# PoE.net
KiCad netlist of a schematic drawn in Altium Designer
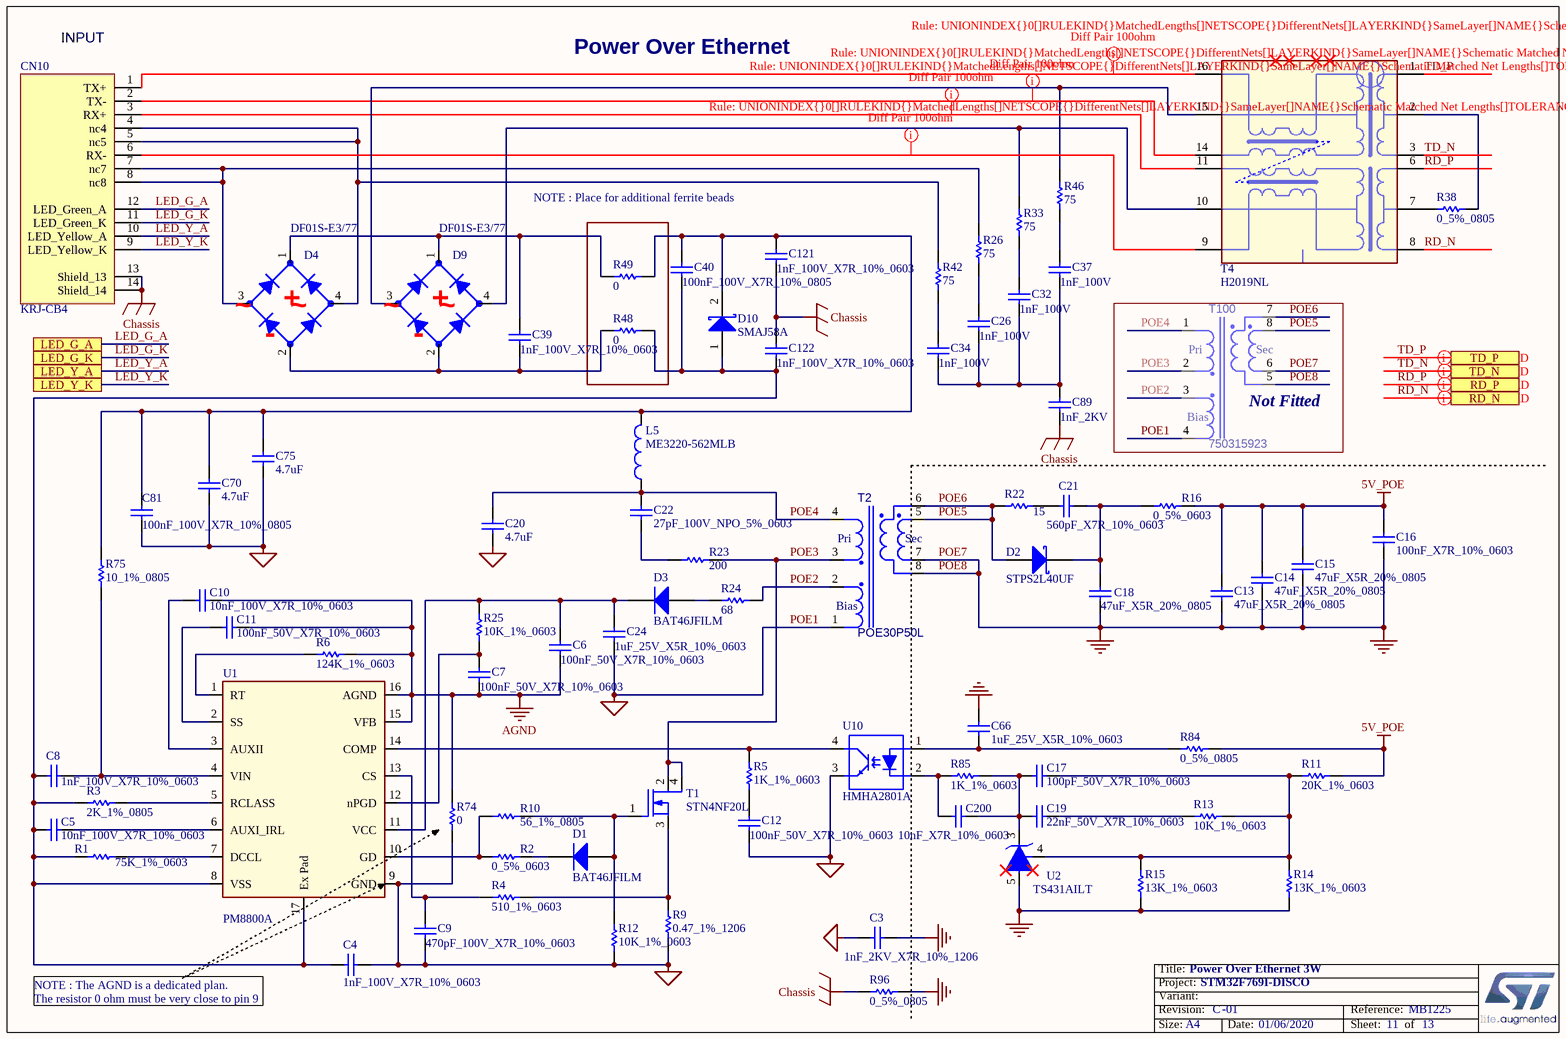
[diagram p0: PoE.SchDoc]

(export (version "E")
  (design (tool "Eeschema 10.0.6"))
  (components
    (comp (ref "C3")
      (value "1nF_2KV_X7R_10%_1206")
      (footprint "1206C")
      (description "Capacitor,1nF,2KV,X7R,10%,1206,YAGEO")
      (libsource (lib "MCD_TOOLS_CAPACITOR") (part "Cap_1nF_2KV_X7R_10%_1206"))
    )
    (comp (ref "C4")
      (value "1nF_100V_X7R_10%_0603")
      (footprint "0603C")
      (description "Capacitor,1nF,100V,X7R,10%,0603,YAGEO")
      (libsource (lib "MCD_TOOLS_CAPACITOR") (part "Cap_1nF_100V_X7R_10%_0603"))
    )
    (comp (ref "C5")
      (value "10nF_100V_X7R_10%_0603")
      (footprint "0603C")
      (description "Capacitor,10nF,100V,X7R,10%,0603,YAGEO")
      (libsource (lib "MCD_TOOLS_CAPACITOR") (part "Cap_10nF_100V_X7R_10%_0603"))
    )
    (comp (ref "C6")
      (value "100nF_50V_X7R_10%_0603")
      (footprint "0603C")
      (description "Capacitor,100nF,50V,X7R,10%,0603,YAGEO")
      (libsource (lib "MCD_TOOLS_CAPACITOR") (part "Cap_100nF_50V_X7R_10%_0603"))
    )
    (comp (ref "C7")
      (value "100nF_50V_X7R_10%_0603")
      (footprint "0603C")
      (description "Capacitor,100nF,50V,X7R,10%,0603,YAGEO")
      (libsource (lib "MCD_TOOLS_CAPACITOR") (part "Cap_100nF_50V_X7R_10%_0603"))
    )
    (comp (ref "C8")
      (value "1nF_100V_X7R_10%_0603")
      (footprint "0603C")
      (description "Capacitor,1nF,100V,X7R,10%,0603,YAGEO")
      (libsource (lib "MCD_TOOLS_CAPACITOR") (part "Cap_1nF_100V_X7R_10%_0603"))
    )
    (comp (ref "C9")
      (value "470pF_100V_X7R_10%_0603")
      (footprint "0603C")
      (description "Capacitor,470pF,100V,X7R,10%,0603,AVX")
      (libsource (lib "MCD_TOOLS_CAPACITOR") (part "Cap_470pF_100V_X7R_10%_0603"))
    )
    (comp (ref "C10")
      (value "10nF_100V_X7R_10%_0603")
      (footprint "0603C")
      (description "Capacitor,10nF,100V,X7R,10%,0603,YAGEO")
      (libsource (lib "MCD_TOOLS_CAPACITOR") (part "Cap_10nF_100V_X7R_10%_0603"))
    )
    (comp (ref "C11")
      (value "100nF_50V_X7R_10%_0603")
      (footprint "0603C")
      (description "Capacitor,100nF,50V,X7R,10%,0603,YAGEO")
      (libsource (lib "MCD_TOOLS_CAPACITOR") (part "Cap_100nF_50V_X7R_10%_0603"))
    )
    (comp (ref "C12")
      (value "100nF_50V_X7R_10%_0603")
      (footprint "0603C")
      (description "Capacitor,100nF,50V,X7R,10%,0603,YAGEO")
      (libsource (lib "MCD_TOOLS_CAPACITOR") (part "Cap_100nF_50V_X7R_10%_0603"))
    )
    (comp (ref "C13")
      (value "47uF_X5R_20%_0805")
      (footprint "0805C")
      (description "Capacitor,47uF,10V,X5R,20%,0805,MURATA")
      (libsource (lib "MCD_TOOLS_CAPACITOR") (part "Cap_47uF_X5R_20%_0805"))
    )
    (comp (ref "C14")
      (value "47uF_X5R_20%_0805")
      (footprint "0805C")
      (description "Capacitor,47uF,10V,X5R,20%,0805,MURATA")
      (libsource (lib "MCD_TOOLS_CAPACITOR") (part "Cap_47uF_X5R_20%_0805"))
    )
    (comp (ref "C15")
      (value "47uF_X5R_20%_0805")
      (footprint "0805C")
      (description "Capacitor,47uF,10V,X5R,20%,0805,MURATA")
      (libsource (lib "MCD_TOOLS_CAPACITOR") (part "Cap_47uF_X5R_20%_0805"))
    )
    (comp (ref "C16")
      (value "100nF_X7R_10%_0603")
      (footprint "0603C")
      (description "Capacitor,100nF,16V,X7R,10%,0603,YAGEO")
      (libsource (lib "MCD_TOOLS_CAPACITOR") (part "Cap_100nF_X7R_10%_0603"))
    )
    (comp (ref "C17")
      (value "100pF_50V_X7R_10%_0603")
      (footprint "0603C")
      (description "Capacitor,100pF,50V,X7R,10%,0603,AVX")
      (libsource (lib "MCD_TOOLS_CAPACITOR") (part "Cap_100pF_50V_X7R_10%_0603"))
    )
    (comp (ref "C18")
      (value "47uF_X5R_20%_0805")
      (footprint "0805C")
      (description "Capacitor,47uF,10V,X5R,20%,0805,MURATA")
      (libsource (lib "MCD_TOOLS_CAPACITOR") (part "Cap_47uF_X5R_20%_0805"))
    )
    (comp (ref "C19")
      (value "22nF_50V_X7R_10%_0603")
      (footprint "0603C")
      (description "Capacitor,22nF,50V,X7R,10%,0603,YAGEO")
      (libsource (lib "MCD_TOOLS_CAPACITOR") (part "Cap_22nF_50V_X7R_10%_0603"))
    )
    (comp (ref "C20")
      (value "4.7uF")
      (footprint "C1210_H2P5")
      (description "Capacitor, MLCC, 4.7uF, 100V, X7S, +/-10%, 1210 , T=2.5mm")
      (fields (field (name "INTERNAL_PART_NUMBER") "MCD-02212") (field (name "MANUFACTURER") "TDK"))
      (libsource (lib "MCD_PARTS_database") (part "Capacitor"))
    )
    (comp (ref "C21")
      (value "560pF_X7R_10%_0603")
      (footprint "0603C")
      (description "Capacitor,560pF,16V,X7R,10%,0603,AVX")
      (libsource (lib "MCD_TOOLS_CAPACITOR") (part "Cap_560pF_X7R_10%_0603"))
    )
    (comp (ref "C22")
      (value "27pF_100V_NPO_5%_0603")
      (footprint "0603C")
      (description "Capacitor,27pF,100V,NPO,5%,0603,YAGEO")
      (libsource (lib "MCD_TOOLS_CAPACITOR") (part "Cap_27pF_100V_NPO_5%_0603"))
    )
    (comp (ref "C24")
      (value "1uF_25V_X5R_10%_0603")
      (footprint "0603C")
      (description "Capacitor,1uF,25V,X5R,10%,0603,YAGEO")
      (libsource (lib "MCD_TOOLS_CAPACITOR") (part "Cap_1uF_25V_X5R_10%_0603"))
    )
    (comp (ref "C26")
      (value "1nF_100V")
      (footprint "0603C")
      (description "Capacitor,1nF,100V,X7R,10%,0603,YAGEO")
      (libsource (lib "MCD_TOOLS_CAPACITOR") (part "Cap_1nF_100V_X7R_10%_0603"))
    )
    (comp (ref "C32")
      (value "1nF_100V")
      (footprint "0603C")
      (description "Capacitor,1nF,100V,X7R,10%,0603,YAGEO")
      (libsource (lib "MCD_TOOLS_CAPACITOR") (part "Cap_1nF_100V_X7R_10%_0603"))
    )
    (comp (ref "C34")
      (value "1nF_100V")
      (footprint "0603C")
      (description "Capacitor,1nF,100V,X7R,10%,0603,YAGEO")
      (libsource (lib "MCD_TOOLS_CAPACITOR") (part "Cap_1nF_100V_X7R_10%_0603"))
    )
    (comp (ref "C37")
      (value "1nF_100V")
      (footprint "0603C")
      (description "Capacitor,1nF,100V,X7R,10%,0603,YAGEO")
      (libsource (lib "MCD_TOOLS_CAPACITOR") (part "Cap_1nF_100V_X7R_10%_0603"))
    )
    (comp (ref "C39")
      (value "1nF_100V_X7R_10%_0603")
      (footprint "0603C")
      (description "Capacitor,1nF,100V,X7R,10%,0603,YAGEO")
      (libsource (lib "MCD_TOOLS_CAPACITOR") (part "Cap_1nF_100V_X7R_10%_0603"))
    )
    (comp (ref "C40")
      (value "100nF_100V_X7R_10%_0805")
      (footprint "0805C")
      (description "Capacitor,100nF,100V,X7R,10%,0805,TDK")
      (libsource (lib "MCD_TOOLS_CAPACITOR") (part "Cap_100nF_100V_X7R_10%_0805"))
    )
    (comp (ref "C66")
      (value "1uF_25V_X5R_10%_0603")
      (footprint "0603C")
      (description "Capacitor,1uF,25V,X5R,10%,0603,YAGEO")
      (libsource (lib "MCD_TOOLS_CAPACITOR") (part "Cap_1uF_25V_X5R_10%_0603"))
    )
    (comp (ref "C70")
      (value "4.7uF")
      (footprint "C1210_H2P5")
      (description "Capacitor, MLCC, 4.7uF, 100V, X7S, +/-10%, 1210 , T=2.5mm")
      (fields (field (name "INTERNAL_PART_NUMBER") "MCD-02212") (field (name "MANUFACTURER") "TDK"))
      (libsource (lib "MCD_PARTS_database") (part "Capacitor"))
    )
    (comp (ref "C75")
      (value "4.7uF")
      (footprint "C1210_H2P5")
      (description "Capacitor, MLCC, 4.7uF, 100V, X7S, +/-10%, 1210 , T=2.5mm")
      (fields (field (name "INTERNAL_PART_NUMBER") "MCD-02212") (field (name "MANUFACTURER") "TDK"))
      (libsource (lib "MCD_PARTS_database") (part "Capacitor"))
    )
    (comp (ref "C81")
      (value "100nF_100V_X7R_10%_0805")
      (footprint "0805C")
      (description "Capacitor,100nF,100V,X7R,10%,0805,TDK")
      (libsource (lib "MCD_TOOLS_CAPACITOR") (part "Cap_100nF_100V_X7R_10%_0805"))
    )
    (comp (ref "C89")
      (value "1nF_2KV")
      (footprint "1206C")
      (description "Capacitor,1nF,2KV,X7R,10%,1206,YAGEO")
      (libsource (lib "MCD_TOOLS_CAPACITOR") (part "Cap_1nF_2KV_X7R_10%_1206"))
    )
    (comp (ref "C121")
      (value "1nF_100V_X7R_10%_0603")
      (footprint "0603C")
      (description "Capacitor,1nF,100V,X7R,10%,0603,YAGEO")
      (libsource (lib "MCD_TOOLS_CAPACITOR") (part "Cap_1nF_100V_X7R_10%_0603"))
    )
    (comp (ref "C122")
      (value "1nF_100V_X7R_10%_0603")
      (footprint "0603C")
      (description "Capacitor,1nF,100V,X7R,10%,0603,YAGEO")
      (libsource (lib "MCD_TOOLS_CAPACITOR") (part "Cap_1nF_100V_X7R_10%_0603"))
    )
    (comp (ref "C200")
      (value "10nF_X7R_10%_0603")
      (footprint "0603C")
      (description "Capacitor,10nF,50V,X7R,10%,0603,YAGEO")
      (libsource (lib "MCD_TOOLS_CAPACITOR") (part "Cap_10nF_X7R_10%_0603"))
    )
    (comp (ref "CN10")
      (value "KRJ-CB4")
      (footprint "RJ45_LED_KRJ-CB4R2GYZNL_EM")
      (description "100 Base-TX (Fast Ethernet)  RJ45 single port (1x1) with LEDS Integrated Connector")
      (libsource (lib "MCD_TOOLS_CONNECTOR") (part "KRJ-CB4"))
    )
    (comp (ref "D1")
      (value "BAT46JFILM")
      (footprint "SOD-323")
      (description "Schottky Single diode(150mA, 100V)")
      (libsource (lib "MCD_TOOLS_MISCELLANEOUS") (part "BAT46JFILM"))
    )
    (comp (ref "D2")
      (value "STPS2L40UF")
      (footprint "SMB")
      (description "Low drop power Schottky rectifier(2A, 40V, 0.34V)")
      (libsource (lib "MCD_TOOLS_MISCELLANEOUS") (part "STPS2L40UF"))
    )
    (comp (ref "D3")
      (value "BAT46JFILM")
      (footprint "SOD-323")
      (description "Schottky Single diode(150mA, 100V)")
      (libsource (lib "MCD_TOOLS_MISCELLANEOUS") (part "BAT46JFILM"))
    )
    (comp (ref "D4")
      (value "DF01S-E3/77")
      (footprint "BRF_VISHAY_DFS_DF01S")
      (description "Surface Mount Bridge Rectifier 1A 100V")
      (fields (field (name "INTERNAL_PART_NUMBER") "MCD-02211") (field (name "MANUFACTURER") "VISHAY"))
      (libsource (lib "MCD_PARTS_database") (part "DF01S_SMD"))
    )
    (comp (ref "D9")
      (value "DF01S-E3/77")
      (footprint "BRF_VISHAY_DFS_DF01S")
      (description "Surface Mount Bridge Rectifier 1A 100V")
      (fields (field (name "INTERNAL_PART_NUMBER") "MCD-02211") (field (name "MANUFACTURER") "VISHAY"))
      (libsource (lib "MCD_PARTS_database") (part "DF01S_SMD"))
    )
    (comp (ref "D10")
      (value "SMAJ58A")
      (footprint "SMA")
      (description "Transil 400W, VRM=58V")
      (libsource (lib "MCD_TOOLS_MISCELLANEOUS") (part "SMAJ58A"))
    )
    (comp (ref "L5")
      (value "ME3220-562MLB")
      (footprint "LSM2_3R2X2R8_H2")
      (description "Power Inductor, 5.6uH, 0.2R, ME3220-562ML, CoilCraft")
      (libsource (lib "MCD_TOOLS_MISCELLANEOUS") (part "ME3220-562ML"))
    )
    (comp (ref "R1")
      (value "75K_1%_0603")
      (footprint "0603R")
      (description "Resistor,75K,0603,1%,YAGEO")
      (libsource (lib "MCD_TOOLS_RESISTOR") (part "Res_75K_1%_0603"))
    )
    (comp (ref "R2")
      (value "0_5%_0603")
      (footprint "0603R-GS")
      (description "Resistor,0,0603,5%,YAGEO")
      (libsource (lib "MCD_TOOLS_RESISTOR") (part "Res_0_5%_0603"))
    )
    (comp (ref "R3")
      (value "2K_1%_0805")
      (footprint "0805R")
      (description "Resistor,2K,0805,1%,YAGEO")
      (libsource (lib "MCD_TOOLS_RESISTOR") (part "Res_2K_1%_0805"))
    )
    (comp (ref "R4")
      (value "510_1%_0603")
      (footprint "0603R")
      (description "Resistor,510,0603,1%,YAGEO")
      (libsource (lib "MCD_TOOLS_RESISTOR") (part "Res_510_1%_0603"))
    )
    (comp (ref "R5")
      (value "1K_1%_0603")
      (footprint "0603R")
      (description "Resistor,1K,0603,1%,YAGEO")
      (libsource (lib "MCD_TOOLS_RESISTOR") (part "Res_1K_1%_0603"))
    )
    (comp (ref "R6")
      (value "124K_1%_0603")
      (footprint "0603R")
      (description "Resistor,124K,0603,1%,YAGEO")
      (libsource (lib "MCD_TOOLS_RESISTOR") (part "Res_124K_1%_0603"))
    )
    (comp (ref "R9")
      (value "0.47_1%_1206")
      (footprint "1206R")
      (description "Resistor,0.47,1206,1%,YAGEO")
      (libsource (lib "MCD_TOOLS_RESISTOR") (part "Res_0.47_1%_1206"))
    )
    (comp (ref "R10")
      (value "56_1%_0805")
      (footprint "0805R")
      (description "Resistor,56,0805,1%,YAGEO")
      (libsource (lib "MCD_TOOLS_RESISTOR") (part "Res_56_1%_0805"))
    )
    (comp (ref "R11")
      (value "20K_1%_0603")
      (footprint "0603R")
      (description "Resistor,20K,0603,1%,YAGEO")
      (libsource (lib "MCD_TOOLS_RESISTOR") (part "Res_20K_1%_0603"))
    )
    (comp (ref "R12")
      (value "10K_1%_0603")
      (footprint "0603R")
      (description "Resistor,10K,0603,1%,YAGEO")
      (libsource (lib "MCD_TOOLS_RESISTOR") (part "Res_10K_1%_0603"))
    )
    (comp (ref "R13")
      (value "10K_1%_0603")
      (footprint "0603R")
      (description "Resistor,10K,0603,1%,YAGEO")
      (libsource (lib "MCD_TOOLS_RESISTOR") (part "Res_10K_1%_0603"))
    )
    (comp (ref "R14")
      (value "13K_1%_0603")
      (footprint "0603R")
      (description "Resistor,13K,0603,1%,YAGEO")
      (libsource (lib "MCD_TOOLS_RESISTOR") (part "Res_13K_1%_0603"))
    )
    (comp (ref "R15")
      (value "13K_1%_0603")
      (footprint "0603R")
      (description "Resistor,13K,0603,1%,YAGEO")
      (libsource (lib "MCD_TOOLS_RESISTOR") (part "Res_13K_1%_0603"))
    )
    (comp (ref "R16")
      (value "0_5%_0603")
      (footprint "0603R-GS")
      (description "Resistor,0,0603,5%,YAGEO")
      (libsource (lib "MCD_TOOLS_RESISTOR") (part "Res_0_5%_0603"))
    )
    (comp (ref "R22")
      (value "15")
      (footprint "0805R")
      (description "Resistor,15,0805,1%,YAGEO")
      (libsource (lib "MCD_TOOLS_RESISTOR") (part "Res_15_1%_0805"))
    )
    (comp (ref "R23")
      (value "200")
      (footprint "1206R")
      (description "Resistor,200,1206,1%,Rohm")
      (libsource (lib "MCD_TOOLS_RESISTOR") (part "Res_200_1%_1206"))
    )
    (comp (ref "R24")
      (value "68")
      (footprint "0805R")
      (description "Resistor,68,0805,1%,YAGEO")
      (libsource (lib "MCD_TOOLS_RESISTOR") (part "Res_68_1%_0805"))
    )
    (comp (ref "R25")
      (value "10K_1%_0603")
      (footprint "0603R")
      (description "Resistor,10K,0603,1%,YAGEO")
      (libsource (lib "MCD_TOOLS_RESISTOR") (part "Res_10K_1%_0603"))
    )
    (comp (ref "R26")
      (value "75")
      (footprint "0805R")
      (description "Resistor,75,0805,1%,YAGEO")
      (libsource (lib "MCD_TOOLS_RESISTOR") (part "Res_75_1%_0805"))
    )
    (comp (ref "R33")
      (value "75")
      (footprint "0805R")
      (description "Resistor,75,0805,1%,YAGEO")
      (libsource (lib "MCD_TOOLS_RESISTOR") (part "Res_75_1%_0805"))
    )
    (comp (ref "R38")
      (value "0_5%_0805")
      (footprint "0805R")
      (description "Resistor,0,0805,5%,YAGEO")
      (libsource (lib "MCD_TOOLS_RESISTOR") (part "Res_0_5%_0805"))
    )
    (comp (ref "R42")
      (value "75")
      (footprint "0805R")
      (description "Resistor,75,0805,1%,YAGEO")
      (libsource (lib "MCD_TOOLS_RESISTOR") (part "Res_75_1%_0805"))
    )
    (comp (ref "R46")
      (value "75")
      (footprint "0805R")
      (description "Resistor,75,0805,1%,YAGEO")
      (libsource (lib "MCD_TOOLS_RESISTOR") (part "Res_75_1%_0805"))
    )
    (comp (ref "R48")
      (value "0")
      (footprint "0805R")
      (description "Resistor,0,0805,5%,YAGEO")
      (libsource (lib "MCD_TOOLS_RESISTOR") (part "Res_0_5%_0805"))
    )
    (comp (ref "R49")
      (value "0")
      (footprint "0805R")
      (description "Resistor,0,0805,5%,YAGEO")
      (libsource (lib "MCD_TOOLS_RESISTOR") (part "Res_0_5%_0805"))
    )
    (comp (ref "R74")
      (value "0")
      (footprint "0603R-GS")
      (description "Resistor,0,0603,5%,YAGEO")
      (libsource (lib "MCD_TOOLS_RESISTOR") (part "Res_0_5%_0603"))
    )
    (comp (ref "R75")
      (value "10_1%_0805")
      (footprint "0805R")
      (description "Resistor,10,0805,1%,Stackpole,1/4W")
      (libsource (lib "MCD_TOOLS_RESISTOR") (part "Res_10_1%_0805"))
    )
    (comp (ref "R84")
      (value "0_5%_0805")
      (footprint "0805R")
      (description "Resistor,0,0805,5%,YAGEO")
      (libsource (lib "MCD_TOOLS_RESISTOR") (part "Res_0_5%_0805"))
    )
    (comp (ref "R85")
      (value "1K_1%_0603")
      (footprint "0603R")
      (description "Resistor,1K,0603,1%,YAGEO")
      (libsource (lib "MCD_TOOLS_RESISTOR") (part "Res_1K_1%_0603"))
    )
    (comp (ref "R96")
      (value "0_5%_0805")
      (footprint "0805R")
      (description "Resistor,0,0805,5%,YAGEO")
      (libsource (lib "MCD_TOOLS_RESISTOR") (part "Res_0_5%_0805"))
    )
    (comp (ref "T1")
      (value "STN4NF20L")
      (footprint "SOT-223")
      (description "N-channel 200 V, 1.1ohm, 1 A, low gate charge STripFET II, Power MOSFET")
      (libsource (lib "MCD_TOOLS_MISCELLANEOUS") (part "STN4NF20L"))
    )
    (comp (ref "T2")
      (value "POE30P50L")
      (footprint "TF_10R9X13R2-12R2X14R4_CPT")
      (description "Flyback Transformers for 3 Watt, PoE applications, CoilCraft Cyntec")
      (fields (field (name "PROVIDED") "Sub Co"))
      (libsource (lib "MCD_TOOLS_MISCELLANEOUS") (part "POE30P_C"))
    )
    (comp (ref "T4")
      (value "H2019NL")
      (footprint "TF_16SM_12R7X9R65")
      (description "10/100BASE-TX VoIP Magnetics Modules, Data Transformer")
      (libsource (lib "MCD_TOOLS_MISCELLANEOUS") (part "H2019"))
    )
    (comp (ref "T100")
      (value "750315923")
      (footprint "TF_8SM_12R04X12R85")
      (description "Flyback Transformers for 3 Watt, PoE applications, Wurth")
      (fields (field (name "PROVIDED") "Sub Co"))
      (libsource (lib "MCD_TOOLS_MISCELLANEOUS") (part "POE30P_W"))
    )
    (comp (ref "U1")
      (value "PM8800A")
      (footprint "TSSOP16_0R65_5x6R4_TP")
      (fields (field (name "PROVIDED") "STM"))
      (libsource (lib "MCD_TOOLS_MISCELLANEOUS") (part "PM8800A"))
    )
    (comp (ref "U2")
      (value "TS431AILT")
      (footprint "SOT23-5")
      (description "Low voltage adjustable shunt reference")
      (libsource (lib "MCD_TOOLS_MISCELLANEOUS") (part "TS431AILT"))
    )
    (comp (ref "U10")
      (value "HMHA2801A")
      (footprint "PC_4SM_1R27_2R5X6R8")
      (description "OPTOISOLATOR 3.7KV TRANSISTOR 4SMD")
      (libsource (lib "mb1225") (part "HMHA2801A"))
    )
  )
  (nets
    (net (code "1") (name "/LED_G_A") (class "Default")
      (node (ref "CN10") (pin "12") (pinfunction "LED_Green_A_12") (pintype "passive"))
    )
    (net (code "2") (name "/LED_G_K") (class "Default")
      (node (ref "CN10") (pin "11") (pinfunction "LED_Green_K_11") (pintype "passive"))
    )
    (net (code "3") (name "/LED_Y_A") (class "Default")
      (node (ref "CN10") (pin "10") (pinfunction "LED_Yellow_A_10") (pintype "passive"))
    )
    (net (code "4") (name "/LED_Y_K") (class "Default")
      (node (ref "CN10") (pin "9") (pinfunction "LED_Yellow_K_9") (pintype "passive"))
    )
    (net (code "5") (name "/POE2") (class "Default")
      (node (ref "R24") (pin "2") (pinfunction "2_2") (pintype "passive"))
      (node (ref "T100") (pin "3") (pinfunction "3_3") (pintype "passive"))
      (node (ref "T2") (pin "2") (pinfunction "2_2") (pintype "passive"))
    )
    (net (code "6") (name "/POE3") (class "Default")
      (node (ref "R23") (pin "2") (pinfunction "2_2") (pintype "passive"))
      (node (ref "T1") (pin "2") (pinfunction "D_2") (pintype "passive"))
      (node (ref "T1") (pin "4") (pinfunction "D_4") (pintype "passive"))
      (node (ref "T100") (pin "2") (pinfunction "2_2") (pintype "passive"))
      (node (ref "T2") (pin "3") (pinfunction "3_3") (pintype "passive"))
    )
    (net (code "7") (name "/POE4") (class "Default")
      (node (ref "C20") (pin "2") (pinfunction "2_2") (pintype "passive"))
      (node (ref "C22") (pin "2") (pinfunction "2_2") (pintype "passive"))
      (node (ref "L5") (pin "1") (pinfunction "1_1") (pintype "passive"))
      (node (ref "T100") (pin "1") (pinfunction "1_1") (pintype "passive"))
      (node (ref "T2") (pin "4") (pinfunction "4_4") (pintype "passive"))
    )
    (net (code "8") (name "/POE5") (class "Default")
      (node (ref "D2") (pin "1") (pinfunction "A_1") (pintype "passive"))
      (node (ref "R22") (pin "1") (pinfunction "1_1") (pintype "passive"))
      (node (ref "T100") (pin "7") (pinfunction "7_7") (pintype "passive"))
      (node (ref "T100") (pin "8") (pinfunction "8_8") (pintype "passive"))
      (node (ref "T2") (pin "5") (pinfunction "5_5") (pintype "passive"))
      (node (ref "T2") (pin "6") (pinfunction "6_6") (pintype "passive"))
    )
    (net (code "9") (name "/RD_N") (class "Default")
      (node (ref "T4") (pin "8") (pinfunction "rd-_8") (pintype "passive"))
    )
    (net (code "10") (name "/RD_P") (class "Default")
      (node (ref "T4") (pin "6") (pinfunction "rd+_6") (pintype "passive"))
    )
    (net (code "11") (name "/TD_N") (class "Default")
      (node (ref "T4") (pin "3") (pinfunction "td-_3") (pintype "passive"))
    )
    (net (code "12") (name "/TD_P") (class "Default")
      (node (ref "T4") (pin "1") (pinfunction "td+_1") (pintype "passive"))
    )
    (net (code "13") (name "5V_POE") (class "Default")
      (node (ref "C13") (pin "2") (pinfunction "2_2") (pintype "passive"))
      (node (ref "C14") (pin "2") (pinfunction "2_2") (pintype "passive"))
      (node (ref "C15") (pin "2") (pinfunction "2_2") (pintype "passive"))
      (node (ref "C16") (pin "2") (pinfunction "2_2") (pintype "passive"))
      (node (ref "R11") (pin "2") (pinfunction "2_2") (pintype "passive"))
      (node (ref "R16") (pin "2") (pinfunction "2_2") (pintype "passive"))
      (node (ref "R84") (pin "2") (pinfunction "2_2") (pintype "passive"))
    )
    (net (code "14") (name "AGND") (class "Default")
      (node (ref "C10") (pin "2") (pinfunction "2_2") (pintype "passive"))
      (node (ref "C11") (pin "2") (pinfunction "2_2") (pintype "passive"))
      (node (ref "C6") (pin "1") (pinfunction "1_1") (pintype "passive"))
      (node (ref "C7") (pin "1") (pinfunction "1_1") (pintype "passive"))
      (node (ref "R6") (pin "2") (pinfunction "2_2") (pintype "passive"))
      (node (ref "R74") (pin "2") (pinfunction "2_2") (pintype "passive"))
      (node (ref "U1") (pin "15") (pinfunction "VFB_15") (pintype "passive"))
      (node (ref "U1") (pin "16") (pinfunction "AGND_16") (pintype "passive"))
    )
    (net (code "15") (name "Chassis") (class "Default")
      (node (ref "C121") (pin "1") (pinfunction "1_1") (pintype "passive"))
      (node (ref "C122") (pin "2") (pinfunction "2_2") (pintype "passive"))
      (node (ref "C89") (pin "1") (pinfunction "1_1") (pintype "passive"))
      (node (ref "CN10") (pin "13") (pinfunction "Shield_13_13") (pintype "passive"))
      (node (ref "CN10") (pin "14") (pinfunction "Shield_14_14") (pintype "passive"))
      (node (ref "R96") (pin "1") (pinfunction "1_1") (pintype "passive"))
    )
    (net (code "16") (name "GND") (class "Default")
      (node (ref "C13") (pin "1") (pinfunction "1_1") (pintype "passive"))
      (node (ref "C14") (pin "1") (pinfunction "1_1") (pintype "passive"))
      (node (ref "C15") (pin "1") (pinfunction "1_1") (pintype "passive"))
      (node (ref "C16") (pin "1") (pinfunction "1_1") (pintype "passive"))
      (node (ref "C18") (pin "1") (pinfunction "1_1") (pintype "passive"))
      (node (ref "C3") (pin "2") (pinfunction "2_2") (pintype "passive"))
      (node (ref "C66") (pin "2") (pinfunction "2_2") (pintype "passive"))
      (node (ref "R14") (pin "1") (pinfunction "1_1") (pintype "passive"))
      (node (ref "R15") (pin "1") (pinfunction "1_1") (pintype "passive"))
      (node (ref "R96") (pin "2") (pinfunction "2_2") (pintype "passive"))
      (node (ref "T100") (pin "5") (pinfunction "5_5") (pintype "passive"))
      (node (ref "T100") (pin "6") (pinfunction "6_6") (pintype "passive"))
      (node (ref "T2") (pin "7") (pinfunction "7_7") (pintype "passive"))
      (node (ref "T2") (pin "8") (pinfunction "8_8") (pintype "passive"))
      (node (ref "U2") (pin "5") (pinfunction "A_5") (pintype "passive"))
    )
    (net (code "17") (name "GND_POWER_IN") (class "Default")
      (node (ref "C12") (pin "1") (pinfunction "1_1") (pintype "passive"))
      (node (ref "C20") (pin "1") (pinfunction "1_1") (pintype "passive"))
      (node (ref "C24") (pin "1") (pinfunction "1_1") (pintype "passive"))
      (node (ref "C3") (pin "1") (pinfunction "1_1") (pintype "passive"))
      (node (ref "C4") (pin "2") (pinfunction "2_2") (pintype "passive"))
      (node (ref "C70") (pin "1") (pinfunction "1_1") (pintype "passive"))
      (node (ref "C75") (pin "1") (pinfunction "1_1") (pintype "passive"))
      (node (ref "C81") (pin "1") (pinfunction "1_1") (pintype "passive"))
      (node (ref "C9") (pin "1") (pinfunction "1_1") (pintype "passive"))
      (node (ref "R12") (pin "1") (pinfunction "1_1") (pintype "passive"))
      (node (ref "R74") (pin "1") (pinfunction "1_1") (pintype "passive"))
      (node (ref "R9") (pin "1") (pinfunction "1_1") (pintype "passive"))
      (node (ref "T100") (pin "4") (pinfunction "4_4") (pintype "passive"))
      (node (ref "T2") (pin "1") (pinfunction "1_1") (pintype "passive"))
      (node (ref "U1") (pin "9") (pinfunction "GND_9") (pintype "passive"))
      (node (ref "U10") (pin "3") (pinfunction "Emitter_3") (pintype "passive"))
    )
    (net (code "18") (name "Net-(C12-Pad2)") (class "Default")
      (node (ref "C12") (pin "2") (pinfunction "2_2") (pintype "passive"))
      (node (ref "R5") (pin "1") (pinfunction "1_1") (pintype "passive"))
    )
    (net (code "19") (name "Net-(C19-Pad2)") (class "Default")
      (node (ref "C19") (pin "2") (pinfunction "2_2") (pintype "passive"))
      (node (ref "R13") (pin "1") (pinfunction "1_1") (pintype "passive"))
    )
    (net (code "20") (name "Net-(C21-Pad1)") (class "Default")
      (node (ref "C21") (pin "1") (pinfunction "1_1") (pintype "passive"))
      (node (ref "R22") (pin "2") (pinfunction "2_2") (pintype "passive"))
    )
    (net (code "21") (name "Net-(C22-Pad1)") (class "Default")
      (node (ref "C22") (pin "1") (pinfunction "1_1") (pintype "passive"))
      (node (ref "R23") (pin "1") (pinfunction "1_1") (pintype "passive"))
    )
    (net (code "22") (name "Net-(C26-Pad1)") (class "Default")
      (node (ref "C26") (pin "1") (pinfunction "1_1") (pintype "passive"))
      (node (ref "C32") (pin "1") (pinfunction "1_1") (pintype "passive"))
      (node (ref "C34") (pin "1") (pinfunction "1_1") (pintype "passive"))
      (node (ref "C37") (pin "1") (pinfunction "1_1") (pintype "passive"))
      (node (ref "C89") (pin "2") (pinfunction "2_2") (pintype "passive"))
    )
    (net (code "23") (name "Net-(C26-Pad2)") (class "Default")
      (node (ref "C26") (pin "2") (pinfunction "2_2") (pintype "passive"))
      (node (ref "R26") (pin "1") (pinfunction "1_1") (pintype "passive"))
    )
    (net (code "24") (name "Net-(C32-Pad2)") (class "Default")
      (node (ref "C32") (pin "2") (pinfunction "2_2") (pintype "passive"))
      (node (ref "R33") (pin "1") (pinfunction "1_1") (pintype "passive"))
    )
    (net (code "25") (name "Net-(C34-Pad2)") (class "Default")
      (node (ref "C34") (pin "2") (pinfunction "2_2") (pintype "passive"))
      (node (ref "R42") (pin "1") (pinfunction "1_1") (pintype "passive"))
    )
    (net (code "26") (name "Net-(C37-Pad2)") (class "Default")
      (node (ref "C37") (pin "2") (pinfunction "2_2") (pintype "passive"))
      (node (ref "R46") (pin "1") (pinfunction "1_1") (pintype "passive"))
    )
    (net (code "27") (name "Net-(CN10-RX+)") (class "Default")
      (node (ref "CN10") (pin "3") (pinfunction "RX+_3") (pintype "passive"))
      (node (ref "T4") (pin "11") (pinfunction "rx1+_11") (pintype "passive"))
    )
    (net (code "28") (name "Net-(CN10-RX-)") (class "Default")
      (node (ref "CN10") (pin "6") (pinfunction "RX-_6") (pintype "passive"))
      (node (ref "T4") (pin "9") (pinfunction "rx-_9") (pintype "passive"))
    )
    (net (code "29") (name "Net-(CN10-TX+)") (class "Default")
      (node (ref "CN10") (pin "1") (pinfunction "TX+_1") (pintype "passive"))
      (node (ref "T4") (pin "16") (pinfunction "tx1+_16") (pintype "passive"))
    )
    (net (code "30") (name "Net-(CN10-TX-)") (class "Default")
      (node (ref "CN10") (pin "2") (pinfunction "TX-_2") (pintype "passive"))
      (node (ref "T4") (pin "14") (pinfunction "tx1-_14") (pintype "passive"))
    )
    (net (code "31") (name "Net-(CN10-nc4)") (class "Default")
      (node (ref "CN10") (pin "4") (pinfunction "nc4_4") (pintype "passive"))
      (node (ref "CN10") (pin "5") (pinfunction "nc5_5") (pintype "passive"))
      (node (ref "D4") (pin "4") (pinfunction "AC_IN_1_4") (pintype "passive"))
      (node (ref "R42") (pin "2") (pinfunction "2_2") (pintype "passive"))
    )
    (net (code "32") (name "Net-(CN10-nc7)") (class "Default")
      (node (ref "CN10") (pin "7") (pinfunction "nc7_7") (pintype "passive"))
      (node (ref "CN10") (pin "8") (pinfunction "nc8_8") (pintype "passive"))
      (node (ref "D4") (pin "3") (pinfunction "AC_IN_2_3") (pintype "passive"))
      (node (ref "R26") (pin "2") (pinfunction "2_2") (pintype "passive"))
    )
    (net (code "33") (name "Net-(D1-A)") (class "Default")
      (node (ref "D1") (pin "1") (pinfunction "A_1") (pintype "passive"))
      (node (ref "R10") (pin "2") (pinfunction "2_2") (pintype "passive"))
      (node (ref "R12") (pin "2") (pinfunction "2_2") (pintype "passive"))
      (node (ref "T1") (pin "1") (pinfunction "G_1") (pintype "passive"))
    )
    (net (code "34") (name "Net-(D1-K)") (class "Default")
      (node (ref "D1") (pin "2") (pinfunction "K_2") (pintype "passive"))
      (node (ref "R2") (pin "2") (pinfunction "2_2") (pintype "passive"))
    )
    (net (code "35") (name "Net-(D2-K)") (class "Default")
      (node (ref "C18") (pin "2") (pinfunction "2_2") (pintype "passive"))
      (node (ref "C21") (pin "2") (pinfunction "2_2") (pintype "passive"))
      (node (ref "D2") (pin "2") (pinfunction "K_2") (pintype "passive"))
      (node (ref "R16") (pin "1") (pinfunction "1_1") (pintype "passive"))
    )
    (net (code "36") (name "Net-(D3-A)") (class "Default")
      (node (ref "D3") (pin "1") (pinfunction "A_1") (pintype "passive"))
      (node (ref "R24") (pin "1") (pinfunction "1_1") (pintype "passive"))
    )
    (net (code "37") (name "Net-(D3-K)") (class "Default")
      (node (ref "C24") (pin "2") (pinfunction "2_2") (pintype "passive"))
      (node (ref "C6") (pin "2") (pinfunction "2_2") (pintype "passive"))
      (node (ref "D3") (pin "2") (pinfunction "K_2") (pintype "passive"))
      (node (ref "R25") (pin "2") (pinfunction "2_2") (pintype "passive"))
      (node (ref "U1") (pin "11") (pinfunction "VCC_11") (pintype "passive"))
    )
    (net (code "38") (name "Net-(D4-DC_OUT_MINUS)") (class "Default")
      (node (ref "C39") (pin "1") (pinfunction "1_1") (pintype "passive"))
      (node (ref "D4") (pin "2") (pinfunction "DC_OUT_MINUS_2") (pintype "passive"))
      (node (ref "D9") (pin "2") (pinfunction "DC_OUT_MINUS_2") (pintype "passive"))
      (node (ref "R48") (pin "1") (pinfunction "1_1") (pintype "passive"))
    )
    (net (code "39") (name "Net-(D4-DC_OUT_PLUS)") (class "Default")
      (node (ref "C39") (pin "2") (pinfunction "2_2") (pintype "passive"))
      (node (ref "D4") (pin "1") (pinfunction "DC_OUT_PLUS_1") (pintype "passive"))
      (node (ref "D9") (pin "1") (pinfunction "DC_OUT_PLUS_1") (pintype "passive"))
      (node (ref "R49") (pin "1") (pinfunction "1_1") (pintype "passive"))
    )
    (net (code "40") (name "Net-(D9-AC_IN_1)") (class "Default")
      (node (ref "D9") (pin "4") (pinfunction "AC_IN_1_4") (pintype "passive"))
      (node (ref "R33") (pin "2") (pinfunction "2_2") (pintype "passive"))
      (node (ref "T4") (pin "10") (pinfunction "rxct_10") (pintype "passive"))
    )
    (net (code "41") (name "Net-(D9-AC_IN_2)") (class "Default")
      (node (ref "D9") (pin "3") (pinfunction "AC_IN_2_3") (pintype "passive"))
      (node (ref "R46") (pin "2") (pinfunction "2_2") (pintype "passive"))
      (node (ref "T4") (pin "15") (pinfunction "txct_15") (pintype "passive"))
    )
    (net (code "42") (name "Net-(D10-A)") (class "Default")
      (node (ref "C122") (pin "1") (pinfunction "1_1") (pintype "passive"))
      (node (ref "C4") (pin "1") (pinfunction "1_1") (pintype "passive"))
      (node (ref "C40") (pin "1") (pinfunction "1_1") (pintype "passive"))
      (node (ref "C5") (pin "1") (pinfunction "1_1") (pintype "passive"))
      (node (ref "C8") (pin "1") (pinfunction "1_1") (pintype "passive"))
      (node (ref "D10") (pin "1") (pinfunction "A_1") (pintype "passive"))
      (node (ref "R1") (pin "1") (pinfunction "1_1") (pintype "passive"))
      (node (ref "R3") (pin "1") (pinfunction "1_1") (pintype "passive"))
      (node (ref "R48") (pin "2") (pinfunction "2_2") (pintype "passive"))
      (node (ref "U1") (pin "17") (pinfunction "Ex_Pad_17") (pintype "passive"))
      (node (ref "U1") (pin "8") (pinfunction "VSS_8") (pintype "passive"))
    )
    (net (code "43") (name "Net-(D10-K)") (class "Default")
      (node (ref "C121") (pin "2") (pinfunction "2_2") (pintype "passive"))
      (node (ref "C40") (pin "2") (pinfunction "2_2") (pintype "passive"))
      (node (ref "C70") (pin "2") (pinfunction "2_2") (pintype "passive"))
      (node (ref "C75") (pin "2") (pinfunction "2_2") (pintype "passive"))
      (node (ref "C81") (pin "2") (pinfunction "2_2") (pintype "passive"))
      (node (ref "D10") (pin "2") (pinfunction "K_2") (pintype "passive"))
      (node (ref "L5") (pin "2") (pinfunction "2_2") (pintype "passive"))
      (node (ref "R49") (pin "2") (pinfunction "2_2") (pintype "passive"))
      (node (ref "R75") (pin "2") (pinfunction "2_2") (pintype "passive"))
    )
    (net (code "44") (name "Net-(T1-S)") (class "Default")
      (node (ref "R4") (pin "2") (pinfunction "2_2") (pintype "passive"))
      (node (ref "R9") (pin "2") (pinfunction "2_2") (pintype "passive"))
      (node (ref "T1") (pin "3") (pinfunction "S_3") (pintype "passive"))
    )
    (net (code "45") (name "Net-(T4-rct)") (class "Default")
      (node (ref "R38") (pin "1") (pinfunction "1_1") (pintype "passive"))
      (node (ref "T4") (pin "7") (pinfunction "rct_7") (pintype "passive"))
    )
    (net (code "46") (name "Net-(T4-tct)") (class "Default")
      (node (ref "R38") (pin "2") (pinfunction "2_2") (pintype "passive"))
      (node (ref "T4") (pin "2") (pinfunction "tct_2") (pintype "passive"))
    )
    (net (code "47") (name "Net-(U1-AUXII)") (class "Default")
      (node (ref "C10") (pin "1") (pinfunction "1_1") (pintype "passive"))
      (node (ref "U1") (pin "3") (pinfunction "AUXII_3") (pintype "passive"))
    )
    (net (code "48") (name "Net-(U1-AUXI_IRL)") (class "Default")
      (node (ref "C5") (pin "2") (pinfunction "2_2") (pintype "passive"))
      (node (ref "U1") (pin "6") (pinfunction "AUXI_IRL_6") (pintype "passive"))
    )
    (net (code "49") (name "Net-(U1-COMP)") (class "Default")
      (node (ref "R5") (pin "2") (pinfunction "2_2") (pintype "passive"))
      (node (ref "U1") (pin "14") (pinfunction "COMP_14") (pintype "passive"))
      (node (ref "U10") (pin "4") (pinfunction "Collector_4") (pintype "passive"))
    )
    (net (code "50") (name "Net-(U1-CS)") (class "Default")
      (node (ref "C9") (pin "2") (pinfunction "2_2") (pintype "passive"))
      (node (ref "R4") (pin "1") (pinfunction "1_1") (pintype "passive"))
      (node (ref "U1") (pin "13") (pinfunction "CS_13") (pintype "passive"))
    )
    (net (code "51") (name "Net-(U1-DCCL)") (class "Default")
      (node (ref "R1") (pin "2") (pinfunction "2_2") (pintype "passive"))
      (node (ref "U1") (pin "7") (pinfunction "DCCL_7") (pintype "passive"))
    )
    (net (code "52") (name "Net-(U1-GD)") (class "Default")
      (node (ref "R10") (pin "1") (pinfunction "1_1") (pintype "passive"))
      (node (ref "R2") (pin "1") (pinfunction "1_1") (pintype "passive"))
      (node (ref "U1") (pin "10") (pinfunction "GD_10") (pintype "passive"))
    )
    (net (code "53") (name "Net-(U1-RCLASS)") (class "Default")
      (node (ref "R3") (pin "2") (pinfunction "2_2") (pintype "passive"))
      (node (ref "U1") (pin "5") (pinfunction "RCLASS_5") (pintype "passive"))
    )
    (net (code "54") (name "Net-(U1-RT)") (class "Default")
      (node (ref "R6") (pin "1") (pinfunction "1_1") (pintype "passive"))
      (node (ref "U1") (pin "1") (pinfunction "RT_1") (pintype "passive"))
    )
    (net (code "55") (name "Net-(U1-SS)") (class "Default")
      (node (ref "C11") (pin "1") (pinfunction "1_1") (pintype "passive"))
      (node (ref "U1") (pin "2") (pinfunction "SS_2") (pintype "passive"))
    )
    (net (code "56") (name "Net-(U1-VIN)") (class "Default")
      (node (ref "C8") (pin "2") (pinfunction "2_2") (pintype "passive"))
      (node (ref "R75") (pin "1") (pinfunction "1_1") (pintype "passive"))
      (node (ref "U1") (pin "4") (pinfunction "VIN_4") (pintype "passive"))
    )
    (net (code "57") (name "Net-(U1-nPGD)") (class "Default")
      (node (ref "C7") (pin "2") (pinfunction "2_2") (pintype "passive"))
      (node (ref "R25") (pin "1") (pinfunction "1_1") (pintype "passive"))
      (node (ref "U1") (pin "12") (pinfunction "nPGD_12") (pintype "passive"))
    )
    (net (code "58") (name "Net-(U2-K)") (class "Default")
      (node (ref "C17") (pin "1") (pinfunction "1_1") (pintype "passive"))
      (node (ref "C19") (pin "1") (pinfunction "1_1") (pintype "passive"))
      (node (ref "C200") (pin "2") (pinfunction "2_2") (pintype "passive"))
      (node (ref "R85") (pin "2") (pinfunction "2_2") (pintype "passive"))
      (node (ref "U2") (pin "3") (pinfunction "K_3") (pintype "passive"))
    )
    (net (code "59") (name "Net-(U2-REF)") (class "Default")
      (node (ref "C17") (pin "2") (pinfunction "2_2") (pintype "passive"))
      (node (ref "R11") (pin "1") (pinfunction "1_1") (pintype "passive"))
      (node (ref "R13") (pin "2") (pinfunction "2_2") (pintype "passive"))
      (node (ref "R14") (pin "2") (pinfunction "2_2") (pintype "passive"))
      (node (ref "R15") (pin "2") (pinfunction "2_2") (pintype "passive"))
      (node (ref "U2") (pin "4") (pinfunction "REF_4") (pintype "passive"))
    )
    (net (code "60") (name "Net-(U10-Anode)") (class "Default")
      (node (ref "C66") (pin "1") (pinfunction "1_1") (pintype "passive"))
      (node (ref "R84") (pin "1") (pinfunction "1_1") (pintype "passive"))
      (node (ref "U10") (pin "1") (pinfunction "Anode_1") (pintype "passive"))
    )
    (net (code "61") (name "Net-(U10-B)") (class "Default")
      (node (ref "C200") (pin "1") (pinfunction "1_1") (pintype "passive"))
      (node (ref "R85") (pin "1") (pinfunction "1_1") (pintype "passive"))
      (node (ref "U10") (pin "2") (pinfunction "B_2") (pintype "passive"))
    )
    (net (code "62") (name "unconnected-(T4-nc_4-Pad4)") (class "Default")
      (node (ref "T4") (pin "4") (pinfunction "nc_4_4") (pintype "passive+no_connect"))
    )
    (net (code "63") (name "unconnected-(T4-nc_5-Pad5)") (class "Default")
      (node (ref "T4") (pin "5") (pinfunction "nc_5_5") (pintype "passive+no_connect"))
    )
    (net (code "64") (name "unconnected-(T4-nc_12-Pad12)") (class "Default")
      (node (ref "T4") (pin "12") (pinfunction "nc_12_12") (pintype "passive+no_connect"))
    )
    (net (code "65") (name "unconnected-(T4-nc_13-Pad13)") (class "Default")
      (node (ref "T4") (pin "13") (pinfunction "nc_13_13") (pintype "passive+no_connect"))
    )
    (net (code "66") (name "unconnected-(U2-nc_1-Pad1)") (class "Default")
      (node (ref "U2") (pin "1") (pinfunction "nc_1_1") (pintype "passive+no_connect"))
    )
    (net (code "67") (name "unconnected-(U2-nc_2-Pad2)") (class "Default")
      (node (ref "U2") (pin "2") (pinfunction "nc_2_2") (pintype "passive+no_connect"))
    )
  )
)
